# design.net
KiCad netlist of a schematic drawn in Altium Designer
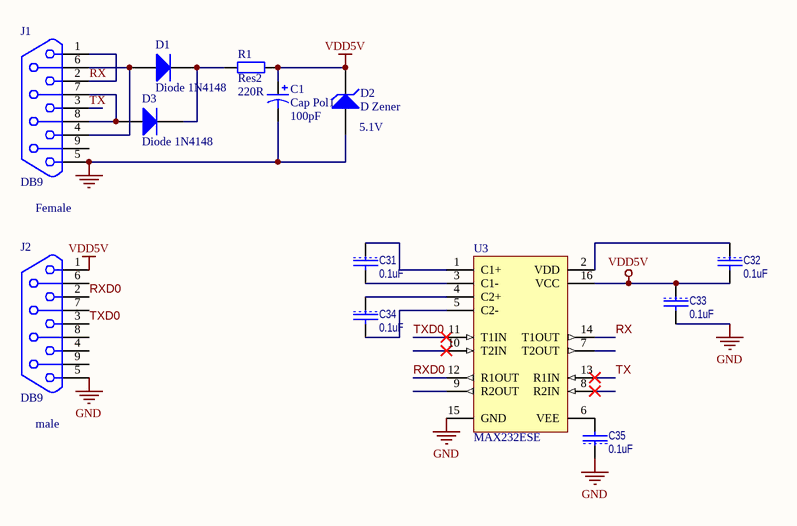
[diagram p0: 串口板.SchDoc]

(export (version "E")
  (design (tool "Eeschema 10.0.6"))
  (components
    (comp (ref "C1")
      (value "Cap Pol1")
      (footprint "Miscellaneous Devices:C1206")
      (description "Polarized Capacitor (Radial)")
      (fields (field (name "ALTIUM_VALUE") "100pF") (field (name "PUBLISHER") "Altium Limited"))
      (libsource (lib "Miscellaneous Devices") (part "Cap Pol1"))
    )
    (comp (ref "C31")
      (value "0.1uF")
      (footprint "Miscellaneous Devices:1608[0603]")
      (description "Capacitor")
      (libsource (lib "*") (part "CAP"))
    )
    (comp (ref "C32")
      (value "0.1uF")
      (footprint "Miscellaneous Devices:1608[0603]")
      (description "Capacitor")
      (libsource (lib "*") (part "CAP"))
    )
    (comp (ref "C33")
      (value "0.1uF")
      (footprint "Miscellaneous Devices:1608[0603]")
      (description "Capacitor")
      (libsource (lib "*") (part "CAP"))
    )
    (comp (ref "C34")
      (value "0.1uF")
      (footprint "Miscellaneous Devices:1608[0603]")
      (description "Capacitor")
      (libsource (lib "*") (part "CAP"))
    )
    (comp (ref "C35")
      (value "0.1uF")
      (footprint "Miscellaneous Devices:1608[0603]")
      (description "Capacitor")
      (libsource (lib "*") (part "CAP"))
    )
    (comp (ref "D1")
      (value "Diode 1N4148")
      (footprint "Miscellaneous Devices:425")
      (description "High Conductance Fast Diode")
      (fields (field (name "PUBLISHER") "Altium Limited"))
      (libsource (lib "Miscellaneous Devices") (part "Diode 1N4148"))
    )
    (comp (ref "D2")
      (value "D Zener")
      (footprint "Miscellaneous Devices:425")
      (description "Zener Diode")
      (fields (field (name "ALTIUM_VALUE") "5.1V") (field (name "PUBLISHER") "Altium Limited"))
      (libsource (lib "Miscellaneous Devices") (part "D Zener"))
    )
    (comp (ref "D3")
      (value "Diode 1N4148")
      (footprint "Miscellaneous Devices:425")
      (description "High Conductance Fast Diode")
      (fields (field (name "PUBLISHER") "Altium Limited"))
      (libsource (lib "Miscellaneous Devices") (part "Diode 1N4148"))
    )
    (comp (ref "J1") (value "DB9") (footprint "DB9BSM") (libsource (lib "*") (part "DB9")))
    (comp (ref "J2") (value "DB9") (footprint "DB9BSM") (libsource (lib "*") (part "DB9")))
    (comp (ref "R1")
      (value "Res2")
      (footprint "Miscellaneous Devices:1608[0603]")
      (description "Resistor")
      (fields (field (name "ALTIUM_VALUE") "220R") (field (name "PUBLISHER") "Altium Limited"))
      (libsource (lib "Miscellaneous Devices") (part "Res2"))
    )
    (comp (ref "U3")
      (value "MAX232ESE")
      (footprint "Miscellaneous Devices:SOIC16_N")
      (description "+5V Powered, Multi-Channel RS-232 Driver/Receiver")
      (fields (field (name "PUBLISHER") "Altium Limited"))
      (libsource (lib "Maxim Communication Transceiver") (part "MAX232ESE"))
    )
  )
  (nets
    (net (code "1") (name "/RX") (class "Default")
      (node (ref "J1") (pin "1") (pinfunction "1_1") (pintype "passive"))
      (node (ref "J1") (pin "2") (pinfunction "2_2") (pintype "passive"))
      (node (ref "U3") (pin "14") (pinfunction "T1OUT_14") (pintype "output"))
    )
    (net (code "2") (name "/RXD0") (class "Default")
      (node (ref "J2") (pin "2") (pinfunction "2_2") (pintype "passive"))
      (node (ref "U3") (pin "12") (pinfunction "R1OUT_12") (pintype "output"))
    )
    (net (code "3") (name "/TX") (class "Default")
      (node (ref "J1") (pin "3") (pinfunction "3_3") (pintype "passive"))
      (node (ref "U3") (pin "13") (pinfunction "R1IN_13") (pintype "input"))
    )
    (net (code "4") (name "/TXD0") (class "Default")
      (node (ref "J2") (pin "3") (pinfunction "3_3") (pintype "passive"))
      (node (ref "U3") (pin "11") (pinfunction "T1IN_11") (pintype "input"))
    )
    (net (code "5") (name "GND") (class "Default")
      (node (ref "C1") (pin "2") (pinfunction "2_2") (pintype "passive"))
      (node (ref "C33") (pin "2") (pinfunction "2_2") (pintype "passive"))
      (node (ref "C35") (pin "1") (pinfunction "1_1") (pintype "passive"))
      (node (ref "D2") (pin "1") (pinfunction "A_1") (pintype "passive"))
      (node (ref "J1") (pin "5") (pinfunction "5_5") (pintype "passive"))
      (node (ref "J2") (pin "5") (pinfunction "5_5") (pintype "passive"))
      (node (ref "U3") (pin "15") (pinfunction "GND_15") (pintype "power_in"))
    )
    (net (code "6") (name "Net-(D1-A)") (class "Default")
      (node (ref "D1") (pin "1") (pinfunction "A_1") (pintype "passive"))
      (node (ref "J1") (pin "4") (pinfunction "4_4") (pintype "passive"))
      (node (ref "J1") (pin "6") (pinfunction "6_6") (pintype "passive"))
    )
    (net (code "7") (name "Net-(D1-K)") (class "Default")
      (node (ref "D1") (pin "2") (pinfunction "K_2") (pintype "passive"))
      (node (ref "D3") (pin "2") (pinfunction "K_2") (pintype "passive"))
      (node (ref "R1") (pin "1") (pinfunction "1_1") (pintype "passive"))
    )
    (net (code "8") (name "Net-(D3-A)") (class "Default")
      (node (ref "D3") (pin "1") (pinfunction "A_1") (pintype "passive"))
      (node (ref "J1") (pin "7") (pinfunction "7_7") (pintype "passive"))
      (node (ref "J1") (pin "8") (pinfunction "8_8") (pintype "passive"))
    )
    (net (code "9") (name "Net-(U3-C1+)") (class "Default")
      (node (ref "C31") (pin "1") (pinfunction "1_1") (pintype "passive"))
      (node (ref "U3") (pin "1") (pinfunction "C1+_1") (pintype "passive"))
    )
    (net (code "10") (name "Net-(U3-C1-)") (class "Default")
      (node (ref "C31") (pin "2") (pinfunction "2_2") (pintype "passive"))
      (node (ref "U3") (pin "3") (pinfunction "C1-_3") (pintype "passive"))
    )
    (net (code "11") (name "Net-(U3-C2+)") (class "Default")
      (node (ref "C34") (pin "1") (pinfunction "1_1") (pintype "passive"))
      (node (ref "U3") (pin "4") (pinfunction "C2+_4") (pintype "passive"))
    )
    (net (code "12") (name "Net-(U3-C2-)") (class "Default")
      (node (ref "C34") (pin "2") (pinfunction "2_2") (pintype "passive"))
      (node (ref "U3") (pin "5") (pinfunction "C2-_5") (pintype "passive"))
    )
    (net (code "13") (name "Net-(U3-VDD)") (class "Default")
      (node (ref "C32") (pin "1") (pinfunction "1_1") (pintype "passive"))
      (node (ref "U3") (pin "2") (pinfunction "VDD_2") (pintype "power_in"))
    )
    (net (code "14") (name "Net-(U3-VEE)") (class "Default")
      (node (ref "C35") (pin "2") (pinfunction "2_2") (pintype "passive"))
      (node (ref "U3") (pin "6") (pinfunction "VEE_6") (pintype "power_in"))
    )
    (net (code "15") (name "VDD5V") (class "Default")
      (node (ref "C1") (pin "1") (pinfunction "1_1") (pintype "passive"))
      (node (ref "C32") (pin "2") (pinfunction "2_2") (pintype "passive"))
      (node (ref "C33") (pin "1") (pinfunction "1_1") (pintype "passive"))
      (node (ref "D2") (pin "2") (pinfunction "K_2") (pintype "passive"))
      (node (ref "J2") (pin "1") (pinfunction "1_1") (pintype "passive"))
      (node (ref "R1") (pin "2") (pinfunction "2_2") (pintype "passive"))
      (node (ref "U3") (pin "16") (pinfunction "VCC_16") (pintype "power_in"))
    )
    (net (code "16") (name "unconnected-(J1-Pad9)") (class "Default")
      (node (ref "J1") (pin "9") (pinfunction "9_9") (pintype "passive"))
    )
    (net (code "17") (name "unconnected-(J2-Pad4)") (class "Default")
      (node (ref "J2") (pin "4") (pinfunction "4_4") (pintype "passive"))
    )
    (net (code "18") (name "unconnected-(J2-Pad6)") (class "Default")
      (node (ref "J2") (pin "6") (pinfunction "6_6") (pintype "passive"))
    )
    (net (code "19") (name "unconnected-(J2-Pad7)") (class "Default")
      (node (ref "J2") (pin "7") (pinfunction "7_7") (pintype "passive"))
    )
    (net (code "20") (name "unconnected-(J2-Pad8)") (class "Default")
      (node (ref "J2") (pin "8") (pinfunction "8_8") (pintype "passive"))
    )
    (net (code "21") (name "unconnected-(J2-Pad9)") (class "Default")
      (node (ref "J2") (pin "9") (pinfunction "9_9") (pintype "passive"))
    )
    (net (code "22") (name "unconnected-(U3-R2IN-Pad8)") (class "Default")
      (node (ref "U3") (pin "8") (pinfunction "R2IN_8") (pintype "input+no_connect"))
    )
    (net (code "23") (name "unconnected-(U3-R2OUT-Pad9)") (class "Default")
      (node (ref "U3") (pin "9") (pinfunction "R2OUT_9") (pintype "output"))
    )
    (net (code "24") (name "unconnected-(U3-T2IN-Pad10)") (class "Default")
      (node (ref "U3") (pin "10") (pinfunction "T2IN_10") (pintype "input+no_connect"))
    )
    (net (code "25") (name "unconnected-(U3-T2OUT-Pad7)") (class "Default")
      (node (ref "U3") (pin "7") (pinfunction "T2OUT_7") (pintype "output"))
    )
  )
)
